# base3-5pin-interface-SDA-SCL-Switch-on-o.net
KiCad netlist of a schematic drawn in EAGLE
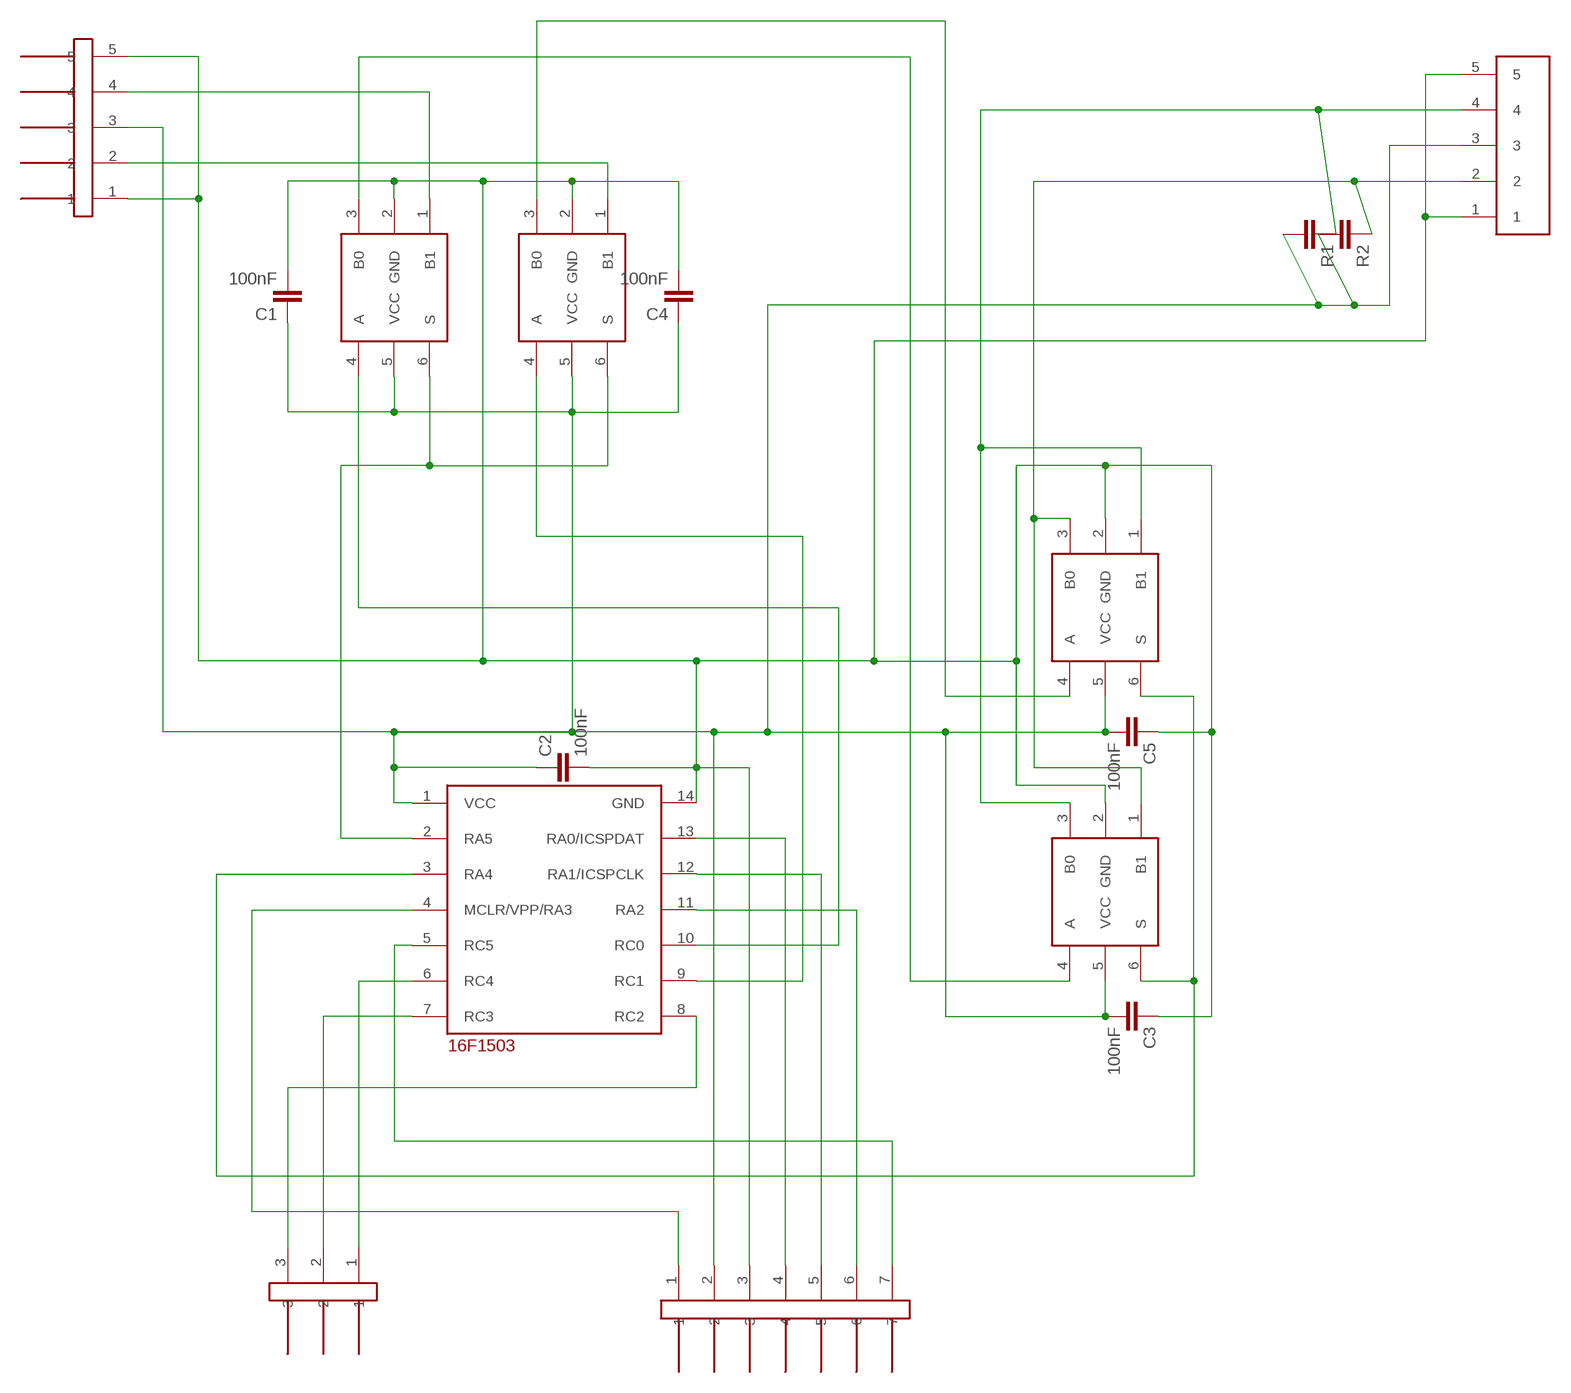
[diagram p0: schematic, sheet 1]

(export (version "E")
  (design (tool "Eeschema 10.0.6"))
  (components
    (comp (ref "C1")
      (value "100nF")
      (footprint "eagle-import:C0805")
      (libsource (lib "eagle-import") (part "resistor_C-EUC0805"))
    )
    (comp (ref "C2")
      (value "100nF")
      (footprint "eagle-import:C0805")
      (libsource (lib "eagle-import") (part "resistor_C-EUC0805"))
    )
    (comp (ref "C3")
      (value "100nF")
      (footprint "eagle-import:C0805")
      (libsource (lib "eagle-import") (part "resistor_C-EUC0805"))
    )
    (comp (ref "C4")
      (value "100nF")
      (footprint "eagle-import:C0805")
      (libsource (lib "eagle-import") (part "resistor_C-EUC0805"))
    )
    (comp (ref "C5")
      (value "100nF")
      (footprint "eagle-import:C0805")
      (libsource (lib "eagle-import") (part "C-EUC0805"))
    )
    (comp (ref "R1")
      (value "C-EUC0805")
      (footprint "eagle-import:C0805")
      (libsource (lib "eagle-import") (part "resistor_C-EUC0805"))
    )
    (comp (ref "R2")
      (value "C-EUC0805")
      (footprint "eagle-import:C0805")
      (libsource (lib "eagle-import") (part "resistor_C-EUC0805"))
    )
    (comp (ref "U$1")
      (value "16F103-TSSOP")
      (footprint "eagle-import:TSSOP14")
      (libsource (lib "eagle-import") (part "16F103-TSSOP"))
    )
    (comp (ref "U$2")
      (value "NC7SB3157P6X")
      (footprint "eagle-import:SC70-6L")
      (libsource (lib "eagle-import") (part "NC7SB3157P6X"))
    )
    (comp (ref "U$3")
      (value "NC7SB3157P6X")
      (footprint "eagle-import:SC70-6L")
      (libsource (lib "eagle-import") (part "NC7SB3157P6X"))
    )
    (comp (ref "U$4")
      (value "JUMPER5")
      (footprint "eagle-import:JUMPER5")
      (libsource (lib "eagle-import") (part "JUMPER5"))
    )
    (comp (ref "U$5")
      (value "JUMPER5F")
      (footprint "eagle-import:JUMPER5F")
      (libsource (lib "eagle-import") (part "JUMPER5F"))
    )
    (comp (ref "U$6")
      (value "NC7SB3157P6X")
      (footprint "eagle-import:SC70-6L")
      (libsource (lib "eagle-import") (part "NC7SB3157P6X"))
    )
    (comp (ref "U$7")
      (value "NC7SB3157P6X")
      (footprint "eagle-import:SC70-6L")
      (libsource (lib "eagle-import") (part "NC7SB3157P6X"))
    )
    (comp (ref "U$8")
      (value "JUMPER7M")
      (footprint "eagle-import:JUMPER7M")
      (libsource (lib "eagle-import") (part "JUMPER7M"))
    )
    (comp (ref "U$9")
      (value "JUMPER3M")
      (footprint "eagle-import:JUMPER3M")
      (libsource (lib "eagle-import") (part "JUMPER3M"))
    )
  )
  (nets
    (net (code "1") (name "Net-(U$1-GND)") (class "Default")
      (node (ref "C1") (pin "2") (pinfunction "2_2") (pintype "passive"))
      (node (ref "C2") (pin "2") (pinfunction "2_2") (pintype "passive"))
      (node (ref "C3") (pin "1") (pinfunction "1_1") (pintype "passive"))
      (node (ref "C4") (pin "2") (pinfunction "2_2") (pintype "passive"))
      (node (ref "C5") (pin "1") (pinfunction "1_1") (pintype "passive"))
      (node (ref "U$1") (pin "14") (pinfunction "GND_14") (pintype "power_in"))
      (node (ref "U$2") (pin "2") (pinfunction "GND_2") (pintype "power_in"))
      (node (ref "U$3") (pin "2") (pinfunction "GND_2") (pintype "power_in"))
      (node (ref "U$4") (pin "1") (pinfunction "1_1") (pintype "bidirectional"))
      (node (ref "U$4") (pin "5") (pinfunction "5_5") (pintype "bidirectional"))
      (node (ref "U$5") (pin "1") (pinfunction "1_1") (pintype "bidirectional"))
      (node (ref "U$5") (pin "5") (pinfunction "5_5") (pintype "bidirectional"))
      (node (ref "U$6") (pin "2") (pinfunction "GND_2") (pintype "power_in"))
      (node (ref "U$7") (pin "2") (pinfunction "GND_2") (pintype "power_in"))
      (node (ref "U$8") (pin "3") (pinfunction "3_3") (pintype "bidirectional"))
    )
    (net (code "2") (name "Net-(U$1-MCLR{slash}VPP{slash}RA3)") (class "Default")
      (node (ref "U$1") (pin "4") (pinfunction "MCLR/VPP/RA3_4") (pintype "bidirectional"))
      (node (ref "U$8") (pin "1") (pinfunction "1_1") (pintype "bidirectional"))
    )
    (net (code "3") (name "Net-(U$1-RA0{slash}ICSPDAT)") (class "Default")
      (node (ref "U$1") (pin "13") (pinfunction "RA0/ICSPDAT_13") (pintype "bidirectional"))
      (node (ref "U$8") (pin "4") (pinfunction "4_4") (pintype "bidirectional"))
    )
    (net (code "4") (name "Net-(U$1-RA1{slash}ICSPCLK)") (class "Default")
      (node (ref "U$1") (pin "12") (pinfunction "RA1/ICSPCLK_12") (pintype "bidirectional"))
      (node (ref "U$8") (pin "5") (pinfunction "5_5") (pintype "bidirectional"))
    )
    (net (code "5") (name "Net-(U$1-RA2)") (class "Default")
      (node (ref "U$1") (pin "11") (pinfunction "RA2_11") (pintype "bidirectional"))
      (node (ref "U$8") (pin "6") (pinfunction "6_6") (pintype "bidirectional"))
    )
    (net (code "6") (name "Net-(U$1-RA4)") (class "Default")
      (node (ref "U$1") (pin "3") (pinfunction "RA4_3") (pintype "bidirectional"))
      (node (ref "U$6") (pin "6") (pinfunction "S_6") (pintype "bidirectional"))
      (node (ref "U$7") (pin "6") (pinfunction "S_6") (pintype "bidirectional"))
    )
    (net (code "7") (name "Net-(U$1-RA5)") (class "Default")
      (node (ref "U$1") (pin "2") (pinfunction "RA5_2") (pintype "bidirectional"))
      (node (ref "U$2") (pin "6") (pinfunction "S_6") (pintype "bidirectional"))
      (node (ref "U$3") (pin "6") (pinfunction "S_6") (pintype "bidirectional"))
    )
    (net (code "8") (name "Net-(U$1-RC0)") (class "Default")
      (node (ref "U$1") (pin "10") (pinfunction "RC0_10") (pintype "bidirectional"))
      (node (ref "U$2") (pin "4") (pinfunction "A_4") (pintype "bidirectional"))
    )
    (net (code "9") (name "Net-(U$1-RC1)") (class "Default")
      (node (ref "U$1") (pin "9") (pinfunction "RC1_9") (pintype "bidirectional"))
      (node (ref "U$3") (pin "4") (pinfunction "A_4") (pintype "bidirectional"))
    )
    (net (code "10") (name "Net-(U$1-RC2)") (class "Default")
      (node (ref "U$1") (pin "8") (pinfunction "RC2_8") (pintype "bidirectional"))
      (node (ref "U$9") (pin "3") (pinfunction "3_3") (pintype "bidirectional"))
    )
    (net (code "11") (name "Net-(U$1-RC3)") (class "Default")
      (node (ref "U$1") (pin "7") (pinfunction "RC3_7") (pintype "bidirectional"))
      (node (ref "U$9") (pin "2") (pinfunction "2_2") (pintype "bidirectional"))
    )
    (net (code "12") (name "Net-(U$1-RC4)") (class "Default")
      (node (ref "U$1") (pin "6") (pinfunction "RC4_6") (pintype "bidirectional"))
      (node (ref "U$9") (pin "1") (pinfunction "1_1") (pintype "bidirectional"))
    )
    (net (code "13") (name "Net-(U$1-RC5)") (class "Default")
      (node (ref "U$1") (pin "5") (pinfunction "RC5_5") (pintype "bidirectional"))
      (node (ref "U$8") (pin "7") (pinfunction "7_7") (pintype "bidirectional"))
    )
    (net (code "14") (name "Net-(U$1-VCC)") (class "Default")
      (node (ref "C1") (pin "1") (pinfunction "1_1") (pintype "passive"))
      (node (ref "C2") (pin "1") (pinfunction "1_1") (pintype "passive"))
      (node (ref "C3") (pin "2") (pinfunction "2_2") (pintype "passive"))
      (node (ref "C4") (pin "1") (pinfunction "1_1") (pintype "passive"))
      (node (ref "C5") (pin "2") (pinfunction "2_2") (pintype "passive"))
      (node (ref "R1") (pin "2") (pinfunction "2_2") (pintype "passive"))
      (node (ref "R2") (pin "2") (pinfunction "2_2") (pintype "passive"))
      (node (ref "U$1") (pin "1") (pinfunction "VCC_1") (pintype "power_in"))
      (node (ref "U$2") (pin "5") (pinfunction "VCC_5") (pintype "power_in"))
      (node (ref "U$3") (pin "5") (pinfunction "VCC_5") (pintype "power_in"))
      (node (ref "U$4") (pin "3") (pinfunction "3_3") (pintype "bidirectional"))
      (node (ref "U$5") (pin "3") (pinfunction "3_3") (pintype "bidirectional"))
      (node (ref "U$6") (pin "5") (pinfunction "VCC_5") (pintype "power_in"))
      (node (ref "U$7") (pin "5") (pinfunction "VCC_5") (pintype "power_in"))
      (node (ref "U$8") (pin "2") (pinfunction "2_2") (pintype "bidirectional"))
    )
    (net (code "15") (name "Net-(U$2-B0)") (class "Default")
      (node (ref "U$2") (pin "3") (pinfunction "B0_3") (pintype "bidirectional"))
      (node (ref "U$7") (pin "4") (pinfunction "A_4") (pintype "bidirectional"))
    )
    (net (code "16") (name "Net-(U$2-B1)") (class "Default")
      (node (ref "U$2") (pin "1") (pinfunction "B1_1") (pintype "bidirectional"))
      (node (ref "U$4") (pin "4") (pinfunction "4_4") (pintype "bidirectional"))
    )
    (net (code "17") (name "Net-(U$3-B0)") (class "Default")
      (node (ref "U$3") (pin "3") (pinfunction "B0_3") (pintype "bidirectional"))
      (node (ref "U$6") (pin "4") (pinfunction "A_4") (pintype "bidirectional"))
    )
    (net (code "18") (name "Net-(U$3-B1)") (class "Default")
      (node (ref "U$3") (pin "1") (pinfunction "B1_1") (pintype "bidirectional"))
      (node (ref "U$4") (pin "2") (pinfunction "2_2") (pintype "bidirectional"))
    )
    (net (code "19") (name "Net-(U$6-B0)") (class "Default")
      (node (ref "R2") (pin "1") (pinfunction "1_1") (pintype "passive"))
      (node (ref "U$5") (pin "2") (pinfunction "2_2") (pintype "bidirectional"))
      (node (ref "U$6") (pin "3") (pinfunction "B0_3") (pintype "bidirectional"))
      (node (ref "U$7") (pin "1") (pinfunction "B1_1") (pintype "bidirectional"))
    )
    (net (code "20") (name "Net-(U$6-B1)") (class "Default")
      (node (ref "R1") (pin "1") (pinfunction "1_1") (pintype "passive"))
      (node (ref "U$5") (pin "4") (pinfunction "4_4") (pintype "bidirectional"))
      (node (ref "U$6") (pin "1") (pinfunction "B1_1") (pintype "bidirectional"))
      (node (ref "U$7") (pin "3") (pinfunction "B0_3") (pintype "bidirectional"))
    )
  )
)
